# schematic.net
KiCad netlist of a schematic drawn in EAGLE
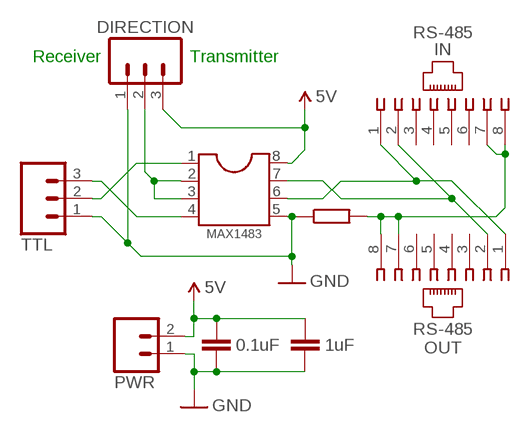
[diagram p0: schematic, sheet 1]

(export (version "E")
  (design (tool "Eeschema 10.0.6"))
  (components
    (comp (ref "B1")
      (value "100R")
      (footprint "eagle-import:0207_10")
      (libsource (lib "eagle-import") (part "R-EU_0207/10"))
    )
    (comp (ref "C1")
      (value "0.1uF")
      (footprint "eagle-import:C025-025X050")
      (libsource (lib "eagle-import") (part "C-EU025-025X050"))
    )
    (comp (ref "C2")
      (value "1uF")
      (footprint "eagle-import:CAP-PTH-5MM")
      (libsource (lib "eagle-import") (part "CAPPTH1"))
    )
    (comp (ref "DIRECTION")
      (value "M03LOCK")
      (footprint "eagle-import:1X03_LOCK")
      (libsource (lib "eagle-import") (part "M03LOCK"))
    )
    (comp (ref "IN")
      (value "RS-485")
      (footprint "eagle-import:215877-4")
      (libsource (lib "eagle-import") (part "215877-4"))
    )
    (comp (ref "MAX1483")
      (value "DIL8S")
      (footprint "eagle-import:SOCKET-08")
      (libsource (lib "eagle-import") (part "DIL8S"))
    )
    (comp (ref "OUT")
      (value "RS-485")
      (footprint "eagle-import:215877-4")
      (libsource (lib "eagle-import") (part "215877-4"))
    )
    (comp (ref "PWR")
      (value "M023.5MM")
      (footprint "eagle-import:SCREWTERMINAL-3.5MM-2")
      (libsource (lib "eagle-import") (part "M023.5MM"))
    )
    (comp (ref "TTL")
      (value "M03SCREW")
      (footprint "eagle-import:SCREWTERMINAL-3.5MM-3")
      (libsource (lib "eagle-import") (part "M03SCREW"))
    )
  )
  (nets
    (net (code "1") (name "5V") (class "Default")
      (node (ref "C1") (pin "1") (pinfunction "1_1") (pintype "passive"))
      (node (ref "C2") (pin "2") (pinfunction "2_2") (pintype "passive"))
      (node (ref "DIRECTION") (pin "3") (pinfunction "3_3") (pintype "passive"))
      (node (ref "MAX1483") (pin "8") (pinfunction "8_8") (pintype "passive"))
      (node (ref "PWR") (pin "2") (pinfunction "2_2") (pintype "passive"))
    )
    (net (code "2") (name "GND") (class "Default")
      (node (ref "B1") (pin "1") (pinfunction "1_1") (pintype "passive"))
      (node (ref "C1") (pin "2") (pinfunction "2_2") (pintype "passive"))
      (node (ref "C2") (pin "1") (pinfunction "1_1") (pintype "passive"))
      (node (ref "DIRECTION") (pin "1") (pinfunction "1_1") (pintype "passive"))
      (node (ref "MAX1483") (pin "5") (pinfunction "5_5") (pintype "passive"))
      (node (ref "PWR") (pin "1") (pinfunction "1_1") (pintype "passive"))
      (node (ref "TTL") (pin "1") (pinfunction "1_1") (pintype "passive"))
    )
    (net (code "3") (name "Net-(B1-Pad2)") (class "Default")
      (node (ref "B1") (pin "2") (pinfunction "2_2") (pintype "passive"))
      (node (ref "IN") (pin "7") (pinfunction "7_7") (pintype "passive"))
      (node (ref "IN") (pin "8") (pinfunction "8_8") (pintype "passive"))
      (node (ref "OUT") (pin "7") (pinfunction "7_7") (pintype "passive"))
      (node (ref "OUT") (pin "8") (pinfunction "8_8") (pintype "passive"))
    )
    (net (code "4") (name "Net-(DIRECTION-Pad2)") (class "Default")
      (node (ref "DIRECTION") (pin "2") (pinfunction "2_2") (pintype "passive"))
      (node (ref "MAX1483") (pin "2") (pinfunction "2_2") (pintype "passive"))
      (node (ref "MAX1483") (pin "3") (pinfunction "3_3") (pintype "passive"))
    )
    (net (code "5") (name "Net-(IN-Pad1)") (class "Default")
      (node (ref "IN") (pin "1") (pinfunction "1_1") (pintype "passive"))
      (node (ref "MAX1483") (pin "6") (pinfunction "6_6") (pintype "passive"))
      (node (ref "OUT") (pin "1") (pinfunction "1_1") (pintype "passive"))
    )
    (net (code "6") (name "Net-(IN-Pad2)") (class "Default")
      (node (ref "IN") (pin "2") (pinfunction "2_2") (pintype "passive"))
      (node (ref "MAX1483") (pin "7") (pinfunction "7_7") (pintype "passive"))
      (node (ref "OUT") (pin "2") (pinfunction "2_2") (pintype "passive"))
    )
    (net (code "7") (name "Net-(MAX1483-Pad1)") (class "Default")
      (node (ref "MAX1483") (pin "1") (pinfunction "1_1") (pintype "passive"))
      (node (ref "TTL") (pin "2") (pinfunction "2_2") (pintype "passive"))
    )
    (net (code "8") (name "Net-(MAX1483-Pad4)") (class "Default")
      (node (ref "MAX1483") (pin "4") (pinfunction "4_4") (pintype "passive"))
      (node (ref "TTL") (pin "3") (pinfunction "3_3") (pintype "passive"))
    )
    (net (code "9") (name "unconnected-(IN-Pad3)") (class "Default")
      (node (ref "IN") (pin "3") (pinfunction "3_3") (pintype "passive"))
    )
    (net (code "10") (name "unconnected-(IN-Pad4)") (class "Default")
      (node (ref "IN") (pin "4") (pinfunction "4_4") (pintype "passive"))
    )
    (net (code "11") (name "unconnected-(IN-Pad5)") (class "Default")
      (node (ref "IN") (pin "5") (pinfunction "5_5") (pintype "passive"))
    )
    (net (code "12") (name "unconnected-(IN-Pad6)") (class "Default")
      (node (ref "IN") (pin "6") (pinfunction "6_6") (pintype "passive"))
    )
    (net (code "13") (name "unconnected-(OUT-Pad3)") (class "Default")
      (node (ref "OUT") (pin "3") (pinfunction "3_3") (pintype "passive"))
    )
    (net (code "14") (name "unconnected-(OUT-Pad4)") (class "Default")
      (node (ref "OUT") (pin "4") (pinfunction "4_4") (pintype "passive"))
    )
    (net (code "15") (name "unconnected-(OUT-Pad5)") (class "Default")
      (node (ref "OUT") (pin "5") (pinfunction "5_5") (pintype "passive"))
    )
    (net (code "16") (name "unconnected-(OUT-Pad6)") (class "Default")
      (node (ref "OUT") (pin "6") (pinfunction "6_6") (pintype "passive"))
    )
  )
)
